# Rigid-Flex.net
KiCad netlist of a schematic drawn in Altium Designer
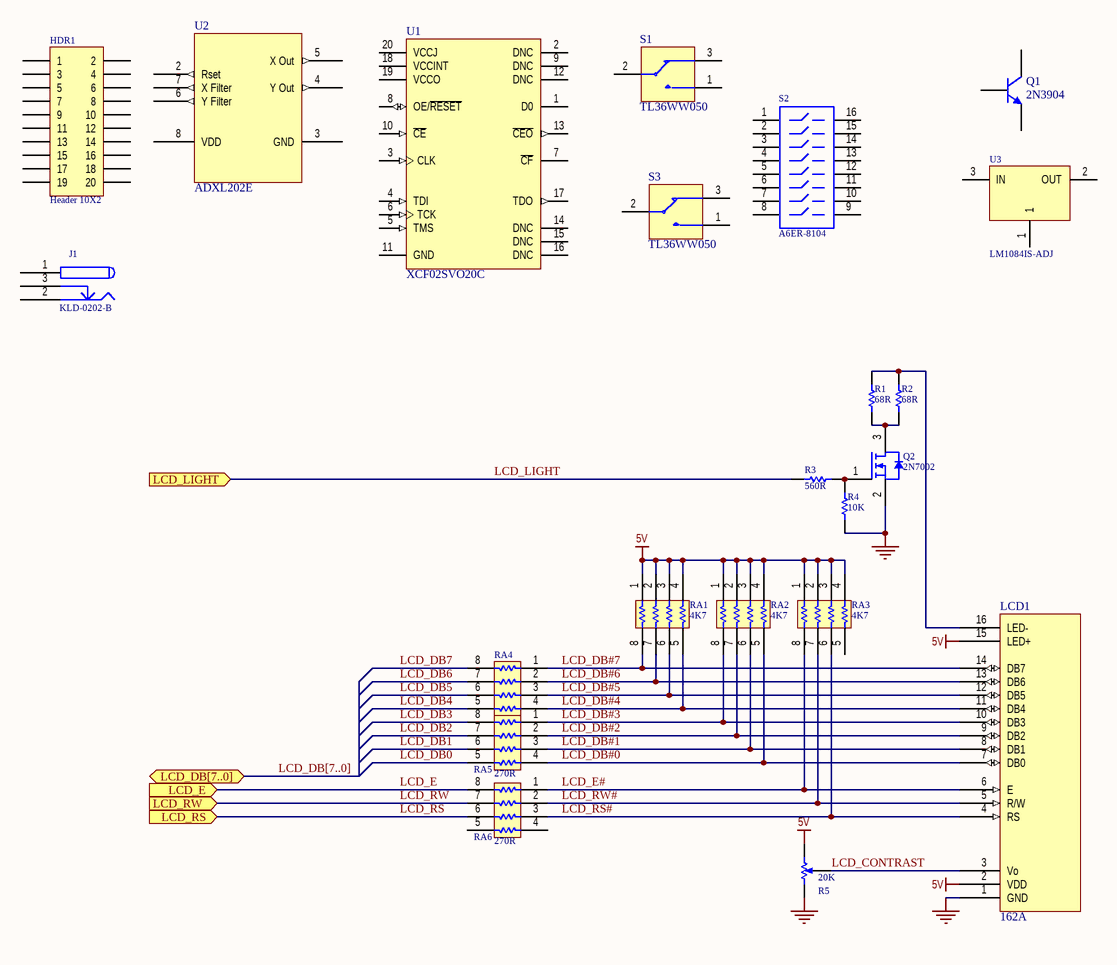
[diagram p0: Rigid-Flex.SchDoc]

(export (version "E")
  (design (tool "Eeschema 10.0.6"))
  (components
    (comp (ref "HDR1")
      (value "Header 10X2")
      (footprint "HDR2X10")
      (description "Header, 10-Pin, Dual row")
      (libsource (lib "Flex") (part "Header 10X2"))
    )
    (comp (ref "J1")
      (value "KLD-0202-B")
      (footprint "KLD-0202")
      (description "Low Voltage Power Supply Connector")
      (fields (field (name "MANUFACTURER") "Kycon"))
      (libsource (lib "Flex") (part "KLD-0202-B"))
    )
    (comp (ref "LCD1")
      (value "162A")
      (footprint "162A")
      (description "16 char * 2 line LCD character display with b/light")
      (libsource (lib "Flex") (part "162A"))
    )
    (comp (ref "Q1")
      (value "2N3904")
      (footprint "TO-92A")
      (description "NPN General Purpose Amplifier")
      (fields (field (name "PUBLISHER") "Altium Limited"))
      (libsource (lib "Miscellaneous Devices") (part "2N3904"))
    )
    (comp (ref "Q2")
      (value "2N7002")
      (footprint "SO-G3")
      (description "N Channel Mosfet")
      (libsource (lib "Flex") (part "2N7002"))
    )
    (comp (ref "R1")
      (value "68R")
      (footprint "CC2012-0805")
      (description "Resistor")
      (libsource (lib "Flex") (part "RES_2"))
    )
    (comp (ref "R2")
      (value "68R")
      (footprint "CC2012-0805")
      (description "Resistor")
      (libsource (lib "Flex") (part "RES_2"))
    )
    (comp (ref "R3")
      (value "560R")
      (footprint "CC2012-0805")
      (description "Resistor")
      (libsource (lib "SpiritLevel_2E") (part "RES"))
    )
    (comp (ref "R4")
      (value "10K")
      (footprint "CR2012-0805")
      (description "Resistor")
      (libsource (lib "Flex") (part "RES"))
    )
    (comp (ref "R5")
      (value "20K")
      (footprint "POT4MM-2")
      (description "Square Trimming Potentiometer")
      (libsource (lib "Flex") (part "RPot SM"))
    )
    (comp (ref "RA1")
      (value "4K7")
      (footprint "MNR34T")
      (description "3216x4 Resistor Array")
      (libsource (lib "") (part "MNR34_1"))
    )
    (comp (ref "RA2")
      (value "4K7")
      (footprint "MNR34T")
      (description "3216x4 Resistor Array")
      (libsource (lib "") (part "MNR34_1"))
    )
    (comp (ref "RA3")
      (value "4K7")
      (footprint "MNR34T")
      (description "3216x4 Resistor Array")
      (libsource (lib "") (part "MNR34_1"))
    )
    (comp (ref "RA4")
      (value "270R")
      (footprint "MNR34")
      (description "3216x4 Resistor Array")
      (libsource (lib "Flex") (part "MNR34"))
    )
    (comp (ref "RA5")
      (value "270R")
      (footprint "MNR34")
      (description "3216x4 Resistor Array")
      (libsource (lib "Flex") (part "MNR34"))
    )
    (comp (ref "RA6")
      (value "270R")
      (footprint "MNR34")
      (description "3216x4 Resistor Array")
      (libsource (lib "Flex") (part "MNR34"))
    )
    (comp (ref "S1")
      (value "TL36WW050")
      (footprint "PCB_SWITCH")
      (description "SPDT Subminiature Toggle Switch")
      (libsource (lib "Flex") (part "PCB_MOUNT_SWITCH"))
    )
    (comp (ref "S2")
      (value "A6ER-8104")
      (footprint "DIP-16-KEY")
      (description "DIP Switch Side actuator long liver Piano Key")
      (libsource (lib "Flex") (part "A6ER-8104"))
    )
    (comp (ref "S3")
      (value "TL36WW050")
      (footprint "PCB_SWITCH")
      (description "SPDT Subminiature Toggle Switch")
      (libsource (lib "Flex") (part "PCB_MOUNT_SWITCH"))
    )
    (comp (ref "U1") (value "XCF02SVO20C") (footprint "VO20") (libsource (lib "Flex") (part "XCF02SVO20C")))
    (comp (ref "U2")
      (value "ADXL202E")
      (footprint "E-8")
      (description "Accelerometer with Digital Output")
      (libsource (lib "Flex") (part "ADXL202E"))
    )
    (comp (ref "U3")
      (value "LM1084IS-ADJ")
      (footprint "TO-263")
      (description "5A Low Dropout Possitive Regulators")
      (libsource (lib "Flex") (part "LM1084IS-ADJ"))
    )
  )
  (nets
    (net (code "1") (name "/LCD_CONTRAST") (class "Default")
      (node (ref "LCD1") (pin "3") (pinfunction "Vo_3") (pintype "tri_state"))
      (node (ref "R5") (pin "W") (pintype "passive"))
    )
    (net (code "2") (name "/LCD_DB#0") (class "Default")
      (node (ref "LCD1") (pin "7") (pinfunction "DB0_7") (pintype "bidirectional"))
      (node (ref "RA2") (pin "5") (pintype "passive"))
      (node (ref "RA5") (pin "4") (pintype "passive"))
    )
    (net (code "3") (name "/LCD_DB#1") (class "Default")
      (node (ref "LCD1") (pin "8") (pinfunction "DB1_8") (pintype "bidirectional"))
      (node (ref "RA2") (pin "6") (pintype "passive"))
      (node (ref "RA5") (pin "3") (pintype "passive"))
    )
    (net (code "4") (name "/LCD_DB#2") (class "Default")
      (node (ref "LCD1") (pin "9") (pinfunction "DB2_9") (pintype "bidirectional"))
      (node (ref "RA2") (pin "7") (pintype "passive"))
      (node (ref "RA5") (pin "2") (pintype "passive"))
    )
    (net (code "5") (name "/LCD_DB#3") (class "Default")
      (node (ref "LCD1") (pin "10") (pinfunction "DB3_10") (pintype "bidirectional"))
      (node (ref "RA2") (pin "8") (pintype "passive"))
      (node (ref "RA5") (pin "1") (pintype "passive"))
    )
    (net (code "6") (name "/LCD_DB#4") (class "Default")
      (node (ref "LCD1") (pin "11") (pinfunction "DB4_11") (pintype "bidirectional"))
      (node (ref "RA1") (pin "5") (pintype "passive"))
      (node (ref "RA4") (pin "4") (pintype "passive"))
    )
    (net (code "7") (name "/LCD_DB#5") (class "Default")
      (node (ref "LCD1") (pin "12") (pinfunction "DB5_12") (pintype "bidirectional"))
      (node (ref "RA1") (pin "6") (pintype "passive"))
      (node (ref "RA4") (pin "3") (pintype "passive"))
    )
    (net (code "8") (name "/LCD_DB#6") (class "Default")
      (node (ref "LCD1") (pin "13") (pinfunction "DB6_13") (pintype "bidirectional"))
      (node (ref "RA1") (pin "7") (pintype "passive"))
      (node (ref "RA4") (pin "2") (pintype "passive"))
    )
    (net (code "9") (name "/LCD_DB#7") (class "Default")
      (node (ref "LCD1") (pin "14") (pinfunction "DB7_14") (pintype "bidirectional"))
      (node (ref "RA1") (pin "8") (pintype "passive"))
      (node (ref "RA4") (pin "1") (pintype "passive"))
    )
    (net (code "10") (name "/LCD_DB0") (class "Default") (node (ref "RA5") (pin "5") (pintype "passive")))
    (net (code "11") (name "/LCD_DB1") (class "Default") (node (ref "RA5") (pin "6") (pintype "passive")))
    (net (code "12") (name "/LCD_DB2") (class "Default") (node (ref "RA5") (pin "7") (pintype "passive")))
    (net (code "13") (name "/LCD_DB3") (class "Default") (node (ref "RA5") (pin "8") (pintype "passive")))
    (net (code "14") (name "/LCD_DB4") (class "Default") (node (ref "RA4") (pin "5") (pintype "passive")))
    (net (code "15") (name "/LCD_DB5") (class "Default") (node (ref "RA4") (pin "6") (pintype "passive")))
    (net (code "16") (name "/LCD_DB6") (class "Default") (node (ref "RA4") (pin "7") (pintype "passive")))
    (net (code "17") (name "/LCD_DB7") (class "Default") (node (ref "RA4") (pin "8") (pintype "passive")))
    (net (code "19") (name "/LCD_E") (class "Default") (node (ref "RA6") (pin "8") (pintype "passive")))
    (net (code "20") (name "/LCD_E#") (class "Default")
      (node (ref "LCD1") (pin "6") (pinfunction "E_6") (pintype "input"))
      (node (ref "RA3") (pin "8") (pintype "passive"))
      (node (ref "RA6") (pin "1") (pintype "passive"))
    )
    (net (code "21") (name "/LCD_LIGHT") (class "Default")
      (node (ref "R3") (pin "1") (pinfunction "1_1") (pintype "passive"))
    )
    (net (code "22") (name "/LCD_RS") (class "Default") (node (ref "RA6") (pin "6") (pintype "passive")))
    (net (code "23") (name "/LCD_RS#") (class "Default")
      (node (ref "LCD1") (pin "4") (pinfunction "RS_4") (pintype "input"))
      (node (ref "RA3") (pin "6") (pintype "passive"))
      (node (ref "RA6") (pin "3") (pintype "passive"))
    )
    (net (code "24") (name "/LCD_RW") (class "Default") (node (ref "RA6") (pin "7") (pintype "passive")))
    (net (code "25") (name "/LCD_RW#") (class "Default")
      (node (ref "LCD1") (pin "5") (pinfunction "R/W_5") (pintype "input"))
      (node (ref "RA3") (pin "7") (pintype "passive"))
      (node (ref "RA6") (pin "2") (pintype "passive"))
    )
    (net (code "26") (name "5V") (class "Default")
      (node (ref "LCD1") (pin "15") (pinfunction "LED+_15") (pintype "power_in"))
      (node (ref "LCD1") (pin "2") (pinfunction "VDD_2") (pintype "power_in"))
      (node (ref "R5") (pin "CW") (pinfunction "+_CW") (pintype "passive"))
      (node (ref "RA1") (pin "1") (pintype "passive"))
      (node (ref "RA1") (pin "2") (pintype "passive"))
      (node (ref "RA1") (pin "3") (pintype "passive"))
      (node (ref "RA1") (pin "4") (pintype "passive"))
      (node (ref "RA2") (pin "1") (pintype "passive"))
      (node (ref "RA2") (pin "2") (pintype "passive"))
      (node (ref "RA2") (pin "3") (pintype "passive"))
      (node (ref "RA2") (pin "4") (pintype "passive"))
      (node (ref "RA3") (pin "1") (pintype "passive"))
      (node (ref "RA3") (pin "2") (pintype "passive"))
      (node (ref "RA3") (pin "3") (pintype "passive"))
      (node (ref "RA3") (pin "4") (pintype "passive"))
    )
    (net (code "27") (name "GND") (class "Default")
      (node (ref "LCD1") (pin "1") (pinfunction "GND_1") (pintype "power_in"))
      (node (ref "Q2") (pin "2") (pintype "passive"))
      (node (ref "R4") (pin "1") (pinfunction "1_1") (pintype "passive"))
      (node (ref "R5") (pin "CCW") (pinfunction "-_CCW") (pintype "passive"))
    )
    (net (code "28") (name "Net-(LCD1-LED-)") (class "Default")
      (node (ref "LCD1") (pin "16") (pinfunction "LED-_16") (pintype "power_in"))
      (node (ref "R1") (pin "1") (pinfunction "1_1") (pintype "passive"))
      (node (ref "R2") (pin "1") (pinfunction "1_1") (pintype "passive"))
    )
    (net (code "29") (name "Net-(Q2-Pad1)") (class "Default")
      (node (ref "Q2") (pin "1") (pintype "passive"))
      (node (ref "R3") (pin "2") (pinfunction "2_2") (pintype "passive"))
      (node (ref "R4") (pin "2") (pinfunction "2_2") (pintype "passive"))
    )
    (net (code "30") (name "Net-(Q2-Pad3)") (class "Default")
      (node (ref "Q2") (pin "3") (pintype "passive"))
      (node (ref "R1") (pin "2") (pinfunction "2_2") (pintype "passive"))
      (node (ref "R2") (pin "2") (pinfunction "2_2") (pintype "passive"))
    )
    (net (code "31") (name "unconnected-(HDR1-Pad1)") (class "Default")
      (node (ref "HDR1") (pin "1") (pinfunction "1_1") (pintype "passive"))
    )
    (net (code "32") (name "unconnected-(HDR1-Pad2)") (class "Default")
      (node (ref "HDR1") (pin "2") (pinfunction "2_2") (pintype "passive"))
    )
    (net (code "33") (name "unconnected-(HDR1-Pad3)") (class "Default")
      (node (ref "HDR1") (pin "3") (pinfunction "3_3") (pintype "passive"))
    )
    (net (code "34") (name "unconnected-(HDR1-Pad4)") (class "Default")
      (node (ref "HDR1") (pin "4") (pinfunction "4_4") (pintype "passive"))
    )
    (net (code "35") (name "unconnected-(HDR1-Pad5)") (class "Default")
      (node (ref "HDR1") (pin "5") (pinfunction "5_5") (pintype "passive"))
    )
    (net (code "36") (name "unconnected-(HDR1-Pad6)") (class "Default")
      (node (ref "HDR1") (pin "6") (pinfunction "6_6") (pintype "passive"))
    )
    (net (code "37") (name "unconnected-(HDR1-Pad7)") (class "Default")
      (node (ref "HDR1") (pin "7") (pinfunction "7_7") (pintype "passive"))
    )
    (net (code "38") (name "unconnected-(HDR1-Pad8)") (class "Default")
      (node (ref "HDR1") (pin "8") (pinfunction "8_8") (pintype "passive"))
    )
    (net (code "39") (name "unconnected-(HDR1-Pad9)") (class "Default")
      (node (ref "HDR1") (pin "9") (pinfunction "9_9") (pintype "passive"))
    )
    (net (code "40") (name "unconnected-(HDR1-Pad10)") (class "Default")
      (node (ref "HDR1") (pin "10") (pinfunction "10_10") (pintype "passive"))
    )
    (net (code "41") (name "unconnected-(HDR1-Pad11)") (class "Default")
      (node (ref "HDR1") (pin "11") (pinfunction "11_11") (pintype "passive"))
    )
    (net (code "42") (name "unconnected-(HDR1-Pad12)") (class "Default")
      (node (ref "HDR1") (pin "12") (pinfunction "12_12") (pintype "passive"))
    )
    (net (code "43") (name "unconnected-(HDR1-Pad13)") (class "Default")
      (node (ref "HDR1") (pin "13") (pinfunction "13_13") (pintype "passive"))
    )
    (net (code "44") (name "unconnected-(HDR1-Pad14)") (class "Default")
      (node (ref "HDR1") (pin "14") (pinfunction "14_14") (pintype "passive"))
    )
    (net (code "45") (name "unconnected-(HDR1-Pad15)") (class "Default")
      (node (ref "HDR1") (pin "15") (pinfunction "15_15") (pintype "passive"))
    )
    (net (code "46") (name "unconnected-(HDR1-Pad16)") (class "Default")
      (node (ref "HDR1") (pin "16") (pinfunction "16_16") (pintype "passive"))
    )
    (net (code "47") (name "unconnected-(HDR1-Pad17)") (class "Default")
      (node (ref "HDR1") (pin "17") (pinfunction "17_17") (pintype "passive"))
    )
    (net (code "48") (name "unconnected-(HDR1-Pad18)") (class "Default")
      (node (ref "HDR1") (pin "18") (pinfunction "18_18") (pintype "passive"))
    )
    (net (code "49") (name "unconnected-(HDR1-Pad19)") (class "Default")
      (node (ref "HDR1") (pin "19") (pinfunction "19_19") (pintype "passive"))
    )
    (net (code "50") (name "unconnected-(HDR1-Pad20)") (class "Default")
      (node (ref "HDR1") (pin "20") (pinfunction "20_20") (pintype "passive"))
    )
    (net (code "51") (name "unconnected-(J1-Pad1)") (class "Default")
      (node (ref "J1") (pin "1") (pintype "power_in"))
    )
    (net (code "52") (name "unconnected-(J1-Pad2)") (class "Default")
      (node (ref "J1") (pin "2") (pintype "power_in"))
    )
    (net (code "53") (name "unconnected-(J1-Pad3)") (class "Default")
      (node (ref "J1") (pin "3") (pintype "power_in"))
    )
    (net (code "54") (name "unconnected-(Q1-B-Pad2)") (class "Default")
      (node (ref "Q1") (pin "2") (pinfunction "B_2") (pintype "passive"))
    )
    (net (code "55") (name "unconnected-(Q1-C-Pad3)") (class "Default")
      (node (ref "Q1") (pin "3") (pinfunction "C_3") (pintype "passive"))
    )
    (net (code "56") (name "unconnected-(Q1-E-Pad1)") (class "Default")
      (node (ref "Q1") (pin "1") (pinfunction "E_1") (pintype "passive"))
    )
    (net (code "57") (name "unconnected-(RA3-Pad5)") (class "Default")
      (node (ref "RA3") (pin "5") (pintype "passive"))
    )
    (net (code "58") (name "unconnected-(RA6-Pad4)") (class "Default")
      (node (ref "RA6") (pin "4") (pintype "passive"))
    )
    (net (code "59") (name "unconnected-(RA6-Pad5)") (class "Default")
      (node (ref "RA6") (pin "5") (pintype "passive"))
    )
    (net (code "60") (name "unconnected-(S1-Pad1)") (class "Default")
      (node (ref "S1") (pin "1") (pintype "passive"))
    )
    (net (code "61") (name "unconnected-(S1-Pad2)") (class "Default")
      (node (ref "S1") (pin "2") (pintype "passive"))
    )
    (net (code "62") (name "unconnected-(S1-Pad3)") (class "Default")
      (node (ref "S1") (pin "3") (pintype "passive"))
    )
    (net (code "63") (name "unconnected-(S2-Pad1)") (class "Default")
      (node (ref "S2") (pin "1") (pinfunction "1_1") (pintype "passive"))
    )
    (net (code "64") (name "unconnected-(S2-Pad2)") (class "Default")
      (node (ref "S2") (pin "2") (pinfunction "2_2") (pintype "passive"))
    )
    (net (code "65") (name "unconnected-(S2-Pad3)") (class "Default")
      (node (ref "S2") (pin "3") (pinfunction "3_3") (pintype "passive"))
    )
    (net (code "66") (name "unconnected-(S2-Pad4)") (class "Default")
      (node (ref "S2") (pin "4") (pinfunction "4_4") (pintype "passive"))
    )
    (net (code "67") (name "unconnected-(S2-Pad5)") (class "Default")
      (node (ref "S2") (pin "5") (pinfunction "5_5") (pintype "passive"))
    )
    (net (code "68") (name "unconnected-(S2-Pad6)") (class "Default")
      (node (ref "S2") (pin "6") (pinfunction "6_6") (pintype "passive"))
    )
    (net (code "69") (name "unconnected-(S2-Pad7)") (class "Default")
      (node (ref "S2") (pin "7") (pinfunction "7_7") (pintype "passive"))
    )
    (net (code "70") (name "unconnected-(S2-Pad8)") (class "Default")
      (node (ref "S2") (pin "8") (pinfunction "8_8") (pintype "passive"))
    )
    (net (code "71") (name "unconnected-(S2-Pad9)") (class "Default")
      (node (ref "S2") (pin "9") (pinfunction "9_9") (pintype "passive"))
    )
    (net (code "72") (name "unconnected-(S2-Pad10)") (class "Default")
      (node (ref "S2") (pin "10") (pinfunction "10_10") (pintype "passive"))
    )
    (net (code "73") (name "unconnected-(S2-Pad11)") (class "Default")
      (node (ref "S2") (pin "11") (pinfunction "11_11") (pintype "passive"))
    )
    (net (code "74") (name "unconnected-(S2-Pad12)") (class "Default")
      (node (ref "S2") (pin "12") (pinfunction "12_12") (pintype "passive"))
    )
    (net (code "75") (name "unconnected-(S2-Pad13)") (class "Default")
      (node (ref "S2") (pin "13") (pinfunction "13_13") (pintype "passive"))
    )
    (net (code "76") (name "unconnected-(S2-Pad14)") (class "Default")
      (node (ref "S2") (pin "14") (pinfunction "14_14") (pintype "passive"))
    )
    (net (code "77") (name "unconnected-(S2-Pad15)") (class "Default")
      (node (ref "S2") (pin "15") (pinfunction "15_15") (pintype "passive"))
    )
    (net (code "78") (name "unconnected-(S2-Pad16)") (class "Default")
      (node (ref "S2") (pin "16") (pinfunction "16_16") (pintype "passive"))
    )
    (net (code "79") (name "unconnected-(S3-Pad1)") (class "Default")
      (node (ref "S3") (pin "1") (pintype "passive"))
    )
    (net (code "80") (name "unconnected-(S3-Pad2)") (class "Default")
      (node (ref "S3") (pin "2") (pintype "passive"))
    )
    (net (code "81") (name "unconnected-(S3-Pad3)") (class "Default")
      (node (ref "S3") (pin "3") (pintype "passive"))
    )
    (net (code "82") (name "unconnected-(U1-CLK-Pad3)") (class "Default")
      (node (ref "U1") (pin "3") (pinfunction "CLK_3") (pintype "input"))
    )
    (net (code "83") (name "unconnected-(U1-D0-Pad1)") (class "Default")
      (node (ref "U1") (pin "1") (pinfunction "D0_1") (pintype "tri_state"))
    )
    (net (code "84") (name "unconnected-(U1-DNC-Pad2)") (class "Default")
      (node (ref "U1") (pin "2") (pinfunction "DNC_2") (pintype "passive"))
    )
    (net (code "85") (name "unconnected-(U1-DNC-Pad9)") (class "Default")
      (node (ref "U1") (pin "9") (pinfunction "DNC_9") (pintype "passive"))
    )
    (net (code "86") (name "unconnected-(U1-DNC-Pad12)") (class "Default")
      (node (ref "U1") (pin "12") (pinfunction "DNC_12") (pintype "passive"))
    )
    (net (code "87") (name "unconnected-(U1-DNC-Pad14)") (class "Default")
      (node (ref "U1") (pin "14") (pinfunction "DNC_14") (pintype "passive"))
    )
    (net (code "88") (name "unconnected-(U1-DNC-Pad15)") (class "Default")
      (node (ref "U1") (pin "15") (pinfunction "DNC_15") (pintype "passive"))
    )
    (net (code "89") (name "unconnected-(U1-DNC-Pad16)") (class "Default")
      (node (ref "U1") (pin "16") (pinfunction "DNC_16") (pintype "passive"))
    )
    (net (code "90") (name "unconnected-(U1-GND-Pad11)") (class "Default")
      (node (ref "U1") (pin "11") (pinfunction "GND_11") (pintype "power_in"))
    )
    (net (code "91") (name "unconnected-(U1-OE{slash}~{RESET}-Pad8)") (class "Default")
      (node (ref "U1") (pin "8") (pinfunction "OE/~{RESET}_8") (pintype "bidirectional"))
    )
    (net (code "92") (name "unconnected-(U1-TCK-Pad6)") (class "Default")
      (node (ref "U1") (pin "6") (pinfunction "TCK_6") (pintype "input"))
    )
    (net (code "93") (name "unconnected-(U1-TDI-Pad4)") (class "Default")
      (node (ref "U1") (pin "4") (pinfunction "TDI_4") (pintype "input"))
    )
    (net (code "94") (name "unconnected-(U1-TDO-Pad17)") (class "Default")
      (node (ref "U1") (pin "17") (pinfunction "TDO_17") (pintype "output"))
    )
    (net (code "95") (name "unconnected-(U1-TMS-Pad5)") (class "Default")
      (node (ref "U1") (pin "5") (pinfunction "TMS_5") (pintype "input"))
    )
    (net (code "96") (name "unconnected-(U1-VCCINT-Pad18)") (class "Default")
      (node (ref "U1") (pin "18") (pinfunction "VCCINT_18") (pintype "power_in"))
    )
    (net (code "97") (name "unconnected-(U1-VCCJ-Pad20)") (class "Default")
      (node (ref "U1") (pin "20") (pinfunction "VCCJ_20") (pintype "power_in"))
    )
    (net (code "98") (name "unconnected-(U1-VCCO-Pad19)") (class "Default")
      (node (ref "U1") (pin "19") (pinfunction "VCCO_19") (pintype "power_in"))
    )
    (net (code "99") (name "unconnected-(U1-~{CEO}-Pad13)") (class "Default")
      (node (ref "U1") (pin "13") (pinfunction "~{CEO}_13") (pintype "output"))
    )
    (net (code "100") (name "unconnected-(U1-~{CE}-Pad10)") (class "Default")
      (node (ref "U1") (pin "10") (pinfunction "~{CE}_10") (pintype "input"))
    )
    (net (code "101") (name "unconnected-(U1-~{CF}-Pad7)") (class "Default")
      (node (ref "U1") (pin "7") (pinfunction "~{CF}_7") (pintype "open_collector"))
    )
    (net (code "102") (name "unconnected-(U2-GND-Pad3)") (class "Default")
      (node (ref "U2") (pin "3") (pinfunction "GND_3") (pintype "power_in"))
    )
    (net (code "103") (name "unconnected-(U2-Rset-Pad2)") (class "Default")
      (node (ref "U2") (pin "2") (pinfunction "Rset_2") (pintype "output"))
    )
    (net (code "104") (name "unconnected-(U2-Self_Test-Pad1)") (class "Default")
      (node (ref "U2") (pin "1") (pinfunction "Self_Test_1") (pintype "input"))
    )
    (net (code "105") (name "unconnected-(U2-VDD-Pad8)") (class "Default")
      (node (ref "U2") (pin "8") (pinfunction "VDD_8") (pintype "power_in"))
    )
    (net (code "106") (name "unconnected-(U2-X_Filter-Pad7)") (class "Default")
      (node (ref "U2") (pin "7") (pinfunction "X_Filter_7") (pintype "output"))
    )
    (net (code "107") (name "unconnected-(U2-X_Out-Pad5)") (class "Default")
      (node (ref "U2") (pin "5") (pinfunction "X_Out_5") (pintype "output"))
    )
    (net (code "108") (name "unconnected-(U2-Y_Filter-Pad6)") (class "Default")
      (node (ref "U2") (pin "6") (pinfunction "Y_Filter_6") (pintype "output"))
    )
    (net (code "109") (name "unconnected-(U2-Y_Out-Pad4)") (class "Default")
      (node (ref "U2") (pin "4") (pinfunction "Y_Out_4") (pintype "output"))
    )
    (net (code "110") (name "unconnected-(U3-IN-Pad3)") (class "Default")
      (node (ref "U3") (pin "3") (pinfunction "IN_3") (pintype "power_in"))
    )
    (net (code "111") (name "unconnected-(U3-OUT-Pad2)") (class "Default")
      (node (ref "U3") (pin "2") (pinfunction "OUT_2") (pintype "power_in"))
    )
    (net (code "112") (name "unconnected-(U3-Pad1)") (class "Default")
      (node (ref "U3") (pin "1") (pinfunction "1_1") (pintype "passive"))
    )
  )
)
